# Sheet1.net
KiCad netlist of a schematic drawn in Altium Designer
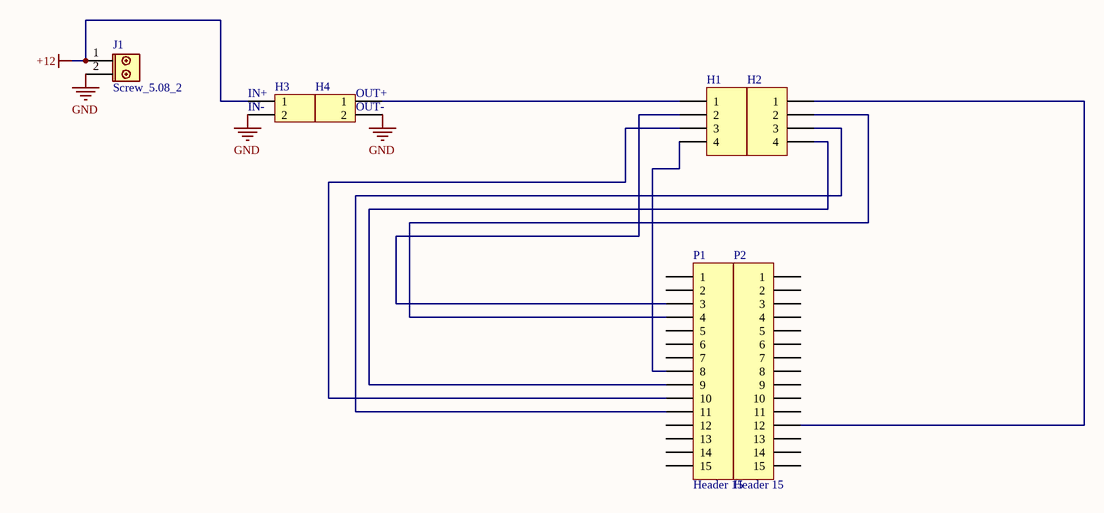
[diagram p0: Sheet1.SchDoc]

(export (version "E")
  (design (tool "Eeschema 10.0.6"))
  (components
    (comp (ref "H1")
      (value "Header 4")
      (footprint "HDR1X4")
      (description "Header, 4-Pin")
      (fields (field (name "MANUFACTURER") "Generic Components"))
      (libsource (lib "MasseyLibs") (part "Header 4"))
    )
    (comp (ref "H2")
      (value "Header 4")
      (footprint "HDR1X4")
      (description "Header, 4-Pin")
      (fields (field (name "MANUFACTURER") "Generic Components"))
      (libsource (lib "") (part "Header 4_1"))
    )
    (comp (ref "H3")
      (value "Header 2")
      (footprint "HDR1X2")
      (description "Header, 2-Pin")
      (fields (field (name "MANUFACTURER") "Generic Components"))
      (libsource (lib "MasseyLibs") (part "Header 2"))
    )
    (comp (ref "H4")
      (value "Header 2")
      (footprint "HDR1X2")
      (description "Header, 2-Pin")
      (fields (field (name "MANUFACTURER") "Generic Components"))
      (libsource (lib "") (part "Header 2_1"))
    )
    (comp (ref "J1")
      (value "Screw_5.08_2")
      (footprint "ScrewTerm_2.54_2")
      (description "2 way screw terminal connector")
      (libsource (lib "MasseyLibs") (part "Screw_5.08_2"))
    )
    (comp (ref "P1")
      (value "Header 15")
      (footprint "HDR1X15")
      (description "Header, 15-Pin")
      (fields (field (name "PUBLISHER") "Altium Limited"))
      (libsource (lib "") (part "Header 15_1"))
    )
    (comp (ref "P2")
      (value "Header 15")
      (footprint "HDR1X15")
      (description "Header, 15-Pin")
      (fields (field (name "PUBLISHER") "Altium Limited"))
      (libsource (lib "Miscellaneous Connectors") (part "Header 15"))
    )
  )
  (nets
    (net (code "1") (name "+12") (class "Default")
      (node (ref "H3") (pin "1") (pinfunction "1_1") (pintype "passive"))
      (node (ref "J1") (pin "1") (pinfunction "1_1") (pintype "passive"))
    )
    (net (code "2") (name "GND") (class "Default")
      (node (ref "H3") (pin "2") (pinfunction "2_2") (pintype "passive"))
      (node (ref "H4") (pin "2") (pinfunction "2_2") (pintype "passive"))
      (node (ref "J1") (pin "2") (pinfunction "2_2") (pintype "passive"))
    )
    (net (code "3") (name "Net-(H1-Pad1)") (class "Default")
      (node (ref "H1") (pin "1") (pinfunction "1_1") (pintype "passive"))
      (node (ref "H4") (pin "1") (pinfunction "1_1") (pintype "passive"))
    )
    (net (code "4") (name "Net-(H1-Pad2)") (class "Default")
      (node (ref "H1") (pin "2") (pinfunction "2_2") (pintype "passive"))
      (node (ref "P1") (pin "3") (pinfunction "3_3") (pintype "passive"))
    )
    (net (code "5") (name "Net-(H1-Pad3)") (class "Default")
      (node (ref "H1") (pin "3") (pinfunction "3_3") (pintype "passive"))
      (node (ref "P1") (pin "10") (pinfunction "10_10") (pintype "passive"))
    )
    (net (code "6") (name "Net-(H1-Pad4)") (class "Default")
      (node (ref "H1") (pin "4") (pinfunction "4_4") (pintype "passive"))
      (node (ref "P1") (pin "8") (pinfunction "8_8") (pintype "passive"))
    )
    (net (code "7") (name "Net-(H2-Pad1)") (class "Default")
      (node (ref "H2") (pin "1") (pinfunction "1_1") (pintype "passive"))
      (node (ref "P2") (pin "12") (pinfunction "12_12") (pintype "passive"))
    )
    (net (code "8") (name "Net-(H2-Pad2)") (class "Default")
      (node (ref "H2") (pin "2") (pinfunction "2_2") (pintype "passive"))
      (node (ref "P1") (pin "4") (pinfunction "4_4") (pintype "passive"))
    )
    (net (code "9") (name "Net-(H2-Pad3)") (class "Default")
      (node (ref "H2") (pin "3") (pinfunction "3_3") (pintype "passive"))
      (node (ref "P1") (pin "11") (pinfunction "11_11") (pintype "passive"))
    )
    (net (code "10") (name "Net-(H2-Pad4)") (class "Default")
      (node (ref "H2") (pin "4") (pinfunction "4_4") (pintype "passive"))
      (node (ref "P1") (pin "9") (pinfunction "9_9") (pintype "passive"))
    )
    (net (code "11") (name "unconnected-(P1-Pad1)") (class "Default")
      (node (ref "P1") (pin "1") (pinfunction "1_1") (pintype "passive"))
    )
    (net (code "12") (name "unconnected-(P1-Pad2)") (class "Default")
      (node (ref "P1") (pin "2") (pinfunction "2_2") (pintype "passive"))
    )
    (net (code "13") (name "unconnected-(P1-Pad5)") (class "Default")
      (node (ref "P1") (pin "5") (pinfunction "5_5") (pintype "passive"))
    )
    (net (code "14") (name "unconnected-(P1-Pad6)") (class "Default")
      (node (ref "P1") (pin "6") (pinfunction "6_6") (pintype "passive"))
    )
    (net (code "15") (name "unconnected-(P1-Pad7)") (class "Default")
      (node (ref "P1") (pin "7") (pinfunction "7_7") (pintype "passive"))
    )
    (net (code "16") (name "unconnected-(P1-Pad12)") (class "Default")
      (node (ref "P1") (pin "12") (pinfunction "12_12") (pintype "passive"))
    )
    (net (code "17") (name "unconnected-(P1-Pad13)") (class "Default")
      (node (ref "P1") (pin "13") (pinfunction "13_13") (pintype "passive"))
    )
    (net (code "18") (name "unconnected-(P1-Pad14)") (class "Default")
      (node (ref "P1") (pin "14") (pinfunction "14_14") (pintype "passive"))
    )
    (net (code "19") (name "unconnected-(P1-Pad15)") (class "Default")
      (node (ref "P1") (pin "15") (pinfunction "15_15") (pintype "passive"))
    )
    (net (code "20") (name "unconnected-(P2-Pad1)") (class "Default")
      (node (ref "P2") (pin "1") (pinfunction "1_1") (pintype "passive"))
    )
    (net (code "21") (name "unconnected-(P2-Pad2)") (class "Default")
      (node (ref "P2") (pin "2") (pinfunction "2_2") (pintype "passive"))
    )
    (net (code "22") (name "unconnected-(P2-Pad3)") (class "Default")
      (node (ref "P2") (pin "3") (pinfunction "3_3") (pintype "passive"))
    )
    (net (code "23") (name "unconnected-(P2-Pad4)") (class "Default")
      (node (ref "P2") (pin "4") (pinfunction "4_4") (pintype "passive"))
    )
    (net (code "24") (name "unconnected-(P2-Pad5)") (class "Default")
      (node (ref "P2") (pin "5") (pinfunction "5_5") (pintype "passive"))
    )
    (net (code "25") (name "unconnected-(P2-Pad6)") (class "Default")
      (node (ref "P2") (pin "6") (pinfunction "6_6") (pintype "passive"))
    )
    (net (code "26") (name "unconnected-(P2-Pad7)") (class "Default")
      (node (ref "P2") (pin "7") (pinfunction "7_7") (pintype "passive"))
    )
    (net (code "27") (name "unconnected-(P2-Pad8)") (class "Default")
      (node (ref "P2") (pin "8") (pinfunction "8_8") (pintype "passive"))
    )
    (net (code "28") (name "unconnected-(P2-Pad9)") (class "Default")
      (node (ref "P2") (pin "9") (pinfunction "9_9") (pintype "passive"))
    )
    (net (code "29") (name "unconnected-(P2-Pad10)") (class "Default")
      (node (ref "P2") (pin "10") (pinfunction "10_10") (pintype "passive"))
    )
    (net (code "30") (name "unconnected-(P2-Pad11)") (class "Default")
      (node (ref "P2") (pin "11") (pinfunction "11_11") (pintype "passive"))
    )
    (net (code "31") (name "unconnected-(P2-Pad13)") (class "Default")
      (node (ref "P2") (pin "13") (pinfunction "13_13") (pintype "passive"))
    )
    (net (code "32") (name "unconnected-(P2-Pad14)") (class "Default")
      (node (ref "P2") (pin "14") (pinfunction "14_14") (pintype "passive"))
    )
    (net (code "33") (name "unconnected-(P2-Pad15)") (class "Default")
      (node (ref "P2") (pin "15") (pinfunction "15_15") (pintype "passive"))
    )
  )
)
